# interface.net
KiCad netlist of a schematic drawn in EAGLE
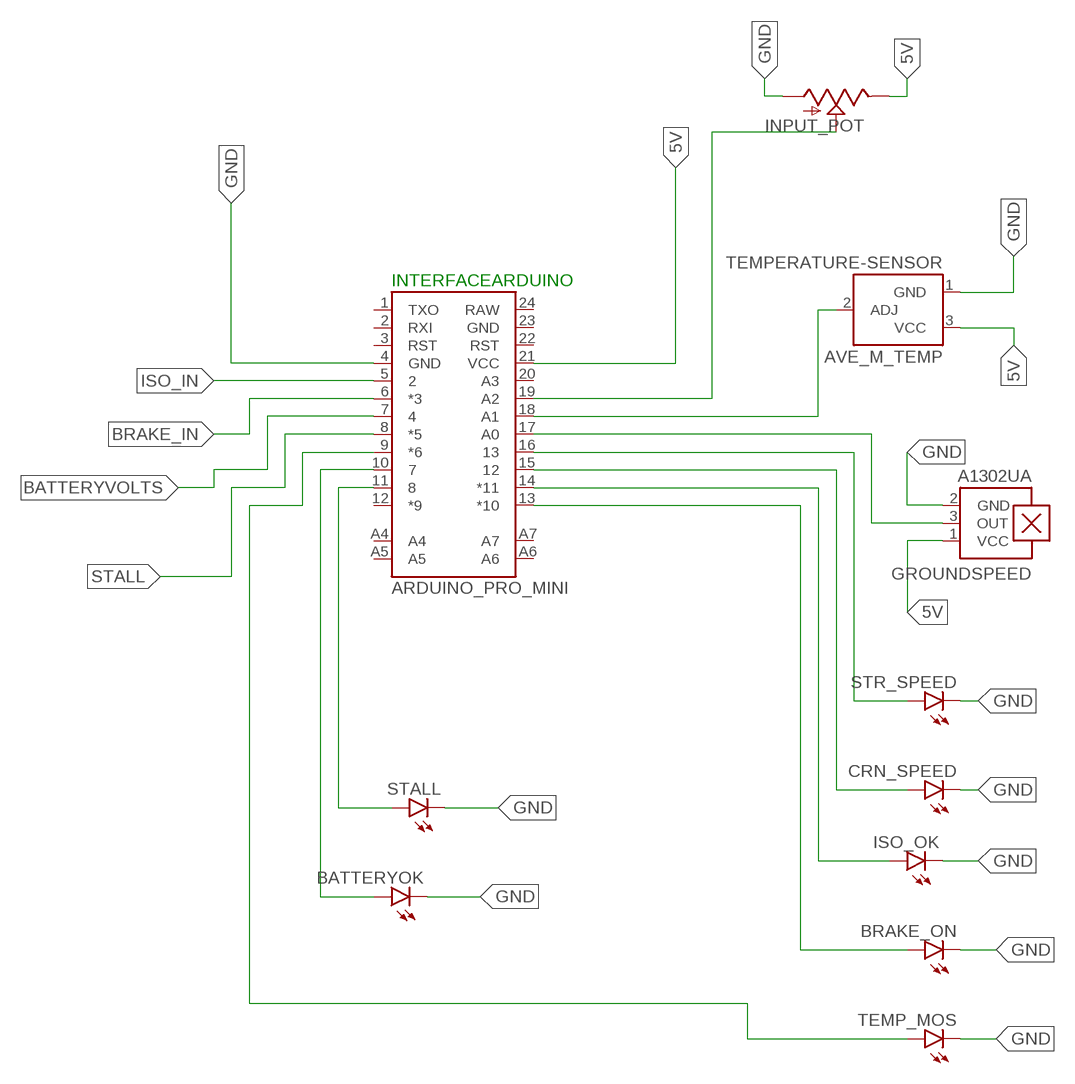
[diagram p0: schematic, sheet 1]

(export (version "E")
  (design (tool "Eeschema 10.0.6"))
  (components
    (comp (ref "AVE_M_TEMP")
      (value "TEMPERATURE-SENSOR")
      (footprint "eagle-import:TO-92")
      (libsource (lib "eagle-import") (part "TEMPERATURE-SENSOR"))
    )
    (comp (ref "BATTERYOK")
      (value "LED3MM")
      (footprint "eagle-import:LED3MM")
      (libsource (lib "eagle-import") (part "LED3MM"))
    )
    (comp (ref "BRAKE_ON")
      (value "LED3MM")
      (footprint "eagle-import:LED3MM")
      (libsource (lib "eagle-import") (part "LED3MM"))
    )
    (comp (ref "CRN_SPEED")
      (value "LED3MM")
      (footprint "eagle-import:LED3MM")
      (libsource (lib "eagle-import") (part "LED3MM"))
    )
    (comp (ref "GROUNDSPEED")
      (value "A1302UA")
      (footprint "eagle-import:SIP3-UA")
      (fields (field (name "MF") "ALLEGRO MICROSYSTEMS, INC.") (field (name "MPN") "A1302EUA-T"))
      (libsource (lib "eagle-import") (part "A13?UA02"))
    )
    (comp (ref "INPUT_POT")
      (value "SLIDER30MM-KIT")
      (footprint "eagle-import:SLIDER-MEDIUM-KIT")
      (libsource (lib "eagle-import") (part "SLIDER30MM-KIT"))
    )
    (comp (ref "INTERFACEARDUINO")
      (value "ARDUINO_PRO_MINI")
      (footprint "eagle-import:ARDUINO_PRO_MINI")
      (libsource (lib "eagle-import") (part "ARDUINO_PRO_MINI"))
    )
    (comp (ref "ISO_OK")
      (value "LED3MM")
      (footprint "eagle-import:LED3MM")
      (libsource (lib "eagle-import") (part "LED3MM"))
    )
    (comp (ref "STALL")
      (value "LED3MM")
      (footprint "eagle-import:LED3MM")
      (libsource (lib "eagle-import") (part "LED3MM"))
    )
    (comp (ref "STR_SPEED")
      (value "LED3MM")
      (footprint "eagle-import:LED3MM")
      (libsource (lib "eagle-import") (part "LED3MM"))
    )
    (comp (ref "TEMP_MOS")
      (value "LED3MM")
      (footprint "eagle-import:LED3MM")
      (libsource (lib "eagle-import") (part "LED3MM"))
    )
  )
  (nets
    (net (code "1") (name "5V") (class "Default")
      (node (ref "AVE_M_TEMP") (pin "3") (pinfunction "VCC_3") (pintype "bidirectional"))
      (node (ref "GROUNDSPEED") (pin "1") (pinfunction "VCC_1") (pintype "power_in"))
      (node (ref "INPUT_POT") (pin "TOP") (pinfunction "E_TOP") (pintype "passive"))
      (node (ref "INTERFACEARDUINO") (pin "21") (pinfunction "VCC_21") (pintype "bidirectional"))
    )
    (net (code "2") (name "BATTERYVOLTS") (class "Default")
      (node (ref "INTERFACEARDUINO") (pin "7") (pinfunction "4_7") (pintype "bidirectional"))
    )
    (net (code "3") (name "BRAKE_IN") (class "Default")
      (node (ref "INTERFACEARDUINO") (pin "6") (pinfunction "*3_6") (pintype "bidirectional"))
    )
    (net (code "4") (name "GND") (class "Default")
      (node (ref "AVE_M_TEMP") (pin "1") (pinfunction "GND_1") (pintype "bidirectional"))
      (node (ref "BATTERYOK") (pin "K") (pinfunction "C_K") (pintype "passive"))
      (node (ref "BRAKE_ON") (pin "K") (pinfunction "C_K") (pintype "passive"))
      (node (ref "CRN_SPEED") (pin "K") (pinfunction "C_K") (pintype "passive"))
      (node (ref "GROUNDSPEED") (pin "2") (pinfunction "GND_2") (pintype "power_in"))
      (node (ref "INPUT_POT") (pin "BOTTOM") (pinfunction "A_BOTTOM") (pintype "passive"))
      (node (ref "INTERFACEARDUINO") (pin "4") (pinfunction "GND_4") (pintype "bidirectional"))
      (node (ref "ISO_OK") (pin "K") (pinfunction "C_K") (pintype "passive"))
      (node (ref "STALL") (pin "K") (pinfunction "C_K") (pintype "passive"))
      (node (ref "STR_SPEED") (pin "K") (pinfunction "C_K") (pintype "passive"))
      (node (ref "TEMP_MOS") (pin "K") (pinfunction "C_K") (pintype "passive"))
    )
    (net (code "5") (name "ISO_IN") (class "Default")
      (node (ref "INTERFACEARDUINO") (pin "5") (pinfunction "2_5") (pintype "bidirectional"))
    )
    (net (code "6") (name "Net-(AVE_M_TEMP-ADJ)") (class "Default")
      (node (ref "AVE_M_TEMP") (pin "2") (pinfunction "ADJ_2") (pintype "bidirectional"))
      (node (ref "INTERFACEARDUINO") (pin "18") (pinfunction "A1_18") (pintype "bidirectional"))
    )
    (net (code "7") (name "Net-(GROUNDSPEED-OUT)") (class "Default")
      (node (ref "GROUNDSPEED") (pin "3") (pinfunction "OUT_3") (pintype "output"))
      (node (ref "INTERFACEARDUINO") (pin "17") (pinfunction "A0_17") (pintype "bidirectional"))
    )
    (net (code "8") (name "Net-(INPUT_POT-S)") (class "Default")
      (node (ref "INPUT_POT") (pin "WIPER") (pinfunction "S_WIPER") (pintype "passive"))
      (node (ref "INTERFACEARDUINO") (pin "19") (pinfunction "A2_19") (pintype "bidirectional"))
    )
    (net (code "9") (name "Net-(INTERFACEARDUINO-*6)") (class "Default")
      (node (ref "INTERFACEARDUINO") (pin "9") (pinfunction "*6_9") (pintype "bidirectional"))
      (node (ref "TEMP_MOS") (pin "A") (pinfunction "A_A") (pintype "passive"))
    )
    (net (code "10") (name "Net-(INTERFACEARDUINO-*10)") (class "Default")
      (node (ref "BRAKE_ON") (pin "A") (pinfunction "A_A") (pintype "passive"))
      (node (ref "INTERFACEARDUINO") (pin "13") (pinfunction "*10_13") (pintype "bidirectional"))
    )
    (net (code "11") (name "Net-(INTERFACEARDUINO-*11)") (class "Default")
      (node (ref "INTERFACEARDUINO") (pin "14") (pinfunction "*11_14") (pintype "bidirectional"))
      (node (ref "ISO_OK") (pin "A") (pinfunction "A_A") (pintype "passive"))
    )
    (net (code "12") (name "Net-(INTERFACEARDUINO-7)") (class "Default")
      (node (ref "BATTERYOK") (pin "A") (pinfunction "A_A") (pintype "passive"))
      (node (ref "INTERFACEARDUINO") (pin "10") (pinfunction "7_10") (pintype "bidirectional"))
    )
    (net (code "13") (name "Net-(INTERFACEARDUINO-8)") (class "Default")
      (node (ref "INTERFACEARDUINO") (pin "11") (pinfunction "8_11") (pintype "bidirectional"))
      (node (ref "STALL") (pin "A") (pinfunction "A_A") (pintype "passive"))
    )
    (net (code "14") (name "Net-(INTERFACEARDUINO-12)") (class "Default")
      (node (ref "CRN_SPEED") (pin "A") (pinfunction "A_A") (pintype "passive"))
      (node (ref "INTERFACEARDUINO") (pin "15") (pinfunction "12_15") (pintype "bidirectional"))
    )
    (net (code "15") (name "Net-(INTERFACEARDUINO-13)") (class "Default")
      (node (ref "INTERFACEARDUINO") (pin "16") (pinfunction "13_16") (pintype "bidirectional"))
      (node (ref "STR_SPEED") (pin "A") (pinfunction "A_A") (pintype "passive"))
    )
    (net (code "16") (name "STALL") (class "Default")
      (node (ref "INTERFACEARDUINO") (pin "8") (pinfunction "*5_8") (pintype "bidirectional"))
    )
    (net (code "17") (name "unconnected-(INTERFACEARDUINO-*9-Pad12)") (class "Default")
      (node (ref "INTERFACEARDUINO") (pin "12") (pinfunction "*9_12") (pintype "bidirectional"))
    )
    (net (code "18") (name "unconnected-(INTERFACEARDUINO-A3-Pad20)") (class "Default")
      (node (ref "INTERFACEARDUINO") (pin "20") (pinfunction "A3_20") (pintype "bidirectional"))
    )
    (net (code "19") (name "unconnected-(INTERFACEARDUINO-GND-Pad23)") (class "Default")
      (node (ref "INTERFACEARDUINO") (pin "23") (pinfunction "GND_23") (pintype "bidirectional"))
    )
    (net (code "20") (name "unconnected-(INTERFACEARDUINO-PadA4)") (class "Default")
      (node (ref "INTERFACEARDUINO") (pin "A4") (pinfunction "A4_A4") (pintype "bidirectional"))
    )
    (net (code "21") (name "unconnected-(INTERFACEARDUINO-PadA5)") (class "Default")
      (node (ref "INTERFACEARDUINO") (pin "A5") (pinfunction "A5_A5") (pintype "bidirectional"))
    )
    (net (code "22") (name "unconnected-(INTERFACEARDUINO-PadA6)") (class "Default")
      (node (ref "INTERFACEARDUINO") (pin "A6") (pinfunction "A6_A6") (pintype "bidirectional"))
    )
    (net (code "23") (name "unconnected-(INTERFACEARDUINO-PadA7)") (class "Default")
      (node (ref "INTERFACEARDUINO") (pin "A7") (pinfunction "A7_A7") (pintype "bidirectional"))
    )
    (net (code "24") (name "unconnected-(INTERFACEARDUINO-RAW-Pad24)") (class "Default")
      (node (ref "INTERFACEARDUINO") (pin "24") (pinfunction "RAW_24") (pintype "bidirectional"))
    )
    (net (code "25") (name "unconnected-(INTERFACEARDUINO-RST-Pad3)") (class "Default")
      (node (ref "INTERFACEARDUINO") (pin "3") (pinfunction "RST_3") (pintype "bidirectional"))
    )
    (net (code "26") (name "unconnected-(INTERFACEARDUINO-RST-Pad22)") (class "Default")
      (node (ref "INTERFACEARDUINO") (pin "22") (pinfunction "RST_22") (pintype "bidirectional"))
    )
    (net (code "27") (name "unconnected-(INTERFACEARDUINO-RXI-Pad2)") (class "Default")
      (node (ref "INTERFACEARDUINO") (pin "2") (pinfunction "RXI_2") (pintype "bidirectional"))
    )
    (net (code "28") (name "unconnected-(INTERFACEARDUINO-TXO-Pad1)") (class "Default")
      (node (ref "INTERFACEARDUINO") (pin "1") (pinfunction "TXO_1") (pintype "bidirectional"))
    )
  )
)
